# DONGLE01.net
KiCad netlist of a schematic drawn in Altium Designer
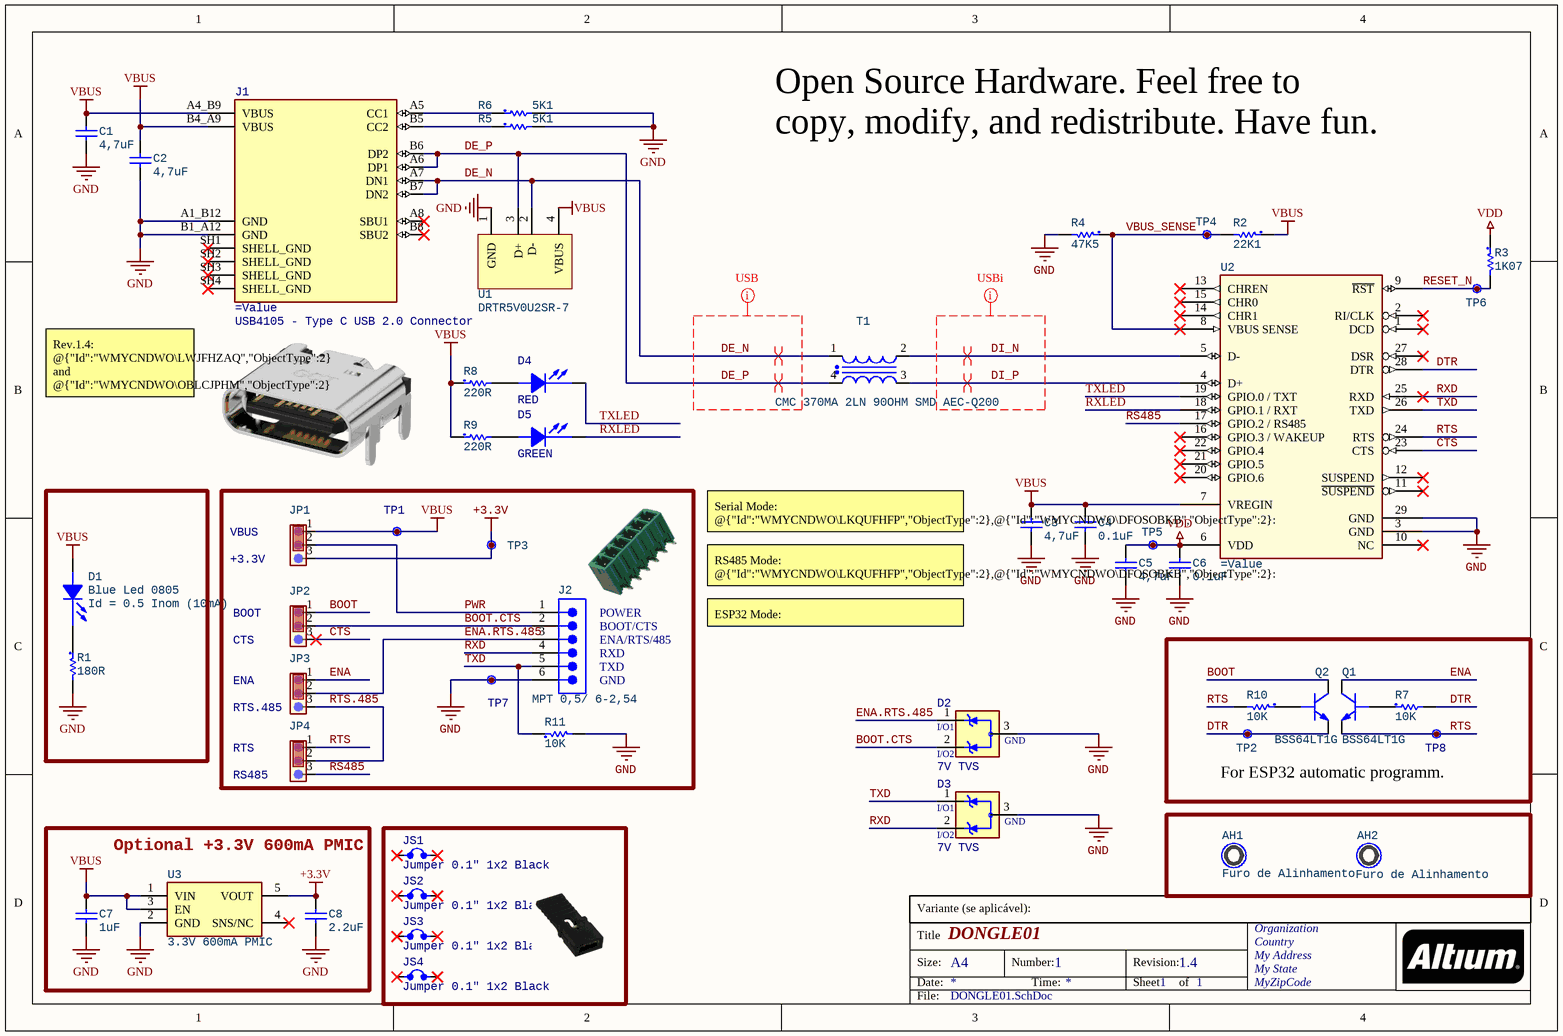
[diagram p0: DONGLE01.SchDoc]

(export (version "E")
  (design (tool "Eeschema 10.0.6"))
  (components
    (comp (ref "AH1")
      (value "Furo de Alinhamento")
      (footprint "AH_2.0MMD")
      (libsource (lib "My_Library") (part "Aligment Hole M2"))
    )
    (comp (ref "AH2")
      (value "Furo de Alinhamento")
      (footprint "AH_2.0MMD")
      (libsource (lib "My_Library") (part "Aligment Hole M2"))
    )
    (comp (ref "C1")
      (value "4,7uF")
      (footprint "C0805")
      (description "4.7 µF ±5% 25V Capacitor de cerâmica X7R 0805 (métrico 2012)")
      (fields (field (name "MANUFACTURER") "KEMET"))
      (libsource (lib "My_Library") (part "CAP"))
    )
    (comp (ref "C2")
      (value "4,7uF")
      (footprint "C0805")
      (description "4.7 µF ±5% 25V Capacitor de cerâmica X7R 0805 (métrico 2012)")
      (fields (field (name "MANUFACTURER") "KEMET"))
      (libsource (lib "My_Library") (part "CAP"))
    )
    (comp (ref "C3")
      (value "4,7uF")
      (footprint "C0805")
      (description "4.7 µF ±5% 25V Capacitor de cerâmica X7R 0805 (métrico 2012)")
      (fields (field (name "MANUFACTURER") "KEMET"))
      (libsource (lib "My_Library") (part "CAP"))
    )
    (comp (ref "C4")
      (value "0.1uF")
      (footprint "C0805")
      (description "0.1 µF ±10% 100V Ceramic Capacitor X7R 0805 (2012 Metric)")
      (fields (field (name "MANUFACTURER") "Murata Electronics"))
      (libsource (lib "My_Library") (part "CAP"))
    )
    (comp (ref "C5")
      (value "4,7uF")
      (footprint "C0805")
      (description "4.7 µF ±5% 25V Capacitor de cerâmica X7R 0805 (métrico 2012)")
      (fields (field (name "MANUFACTURER") "KEMET"))
      (libsource (lib "My_Library") (part "CAP"))
    )
    (comp (ref "C6")
      (value "0.1uF")
      (footprint "C0805")
      (description "0.1 µF ±10% 100V Ceramic Capacitor X7R 0805 (2012 Metric)")
      (fields (field (name "MANUFACTURER") "Murata Electronics"))
      (libsource (lib "My_Library") (part "CAP"))
    )
    (comp (ref "C7")
      (value "1uF")
      (footprint "C0805")
      (description "1 µF ±5% 16V Ceramic Capacitor X7R 0805 (2012 Metric)")
      (fields (field (name "MANUFACTURER") "KEMET"))
      (libsource (lib "My_Library") (part "CAP"))
    )
    (comp (ref "C8")
      (value "2.2uF")
      (footprint "C0805")
      (description "2.2 µF ±5% 16V Ceramic Capacitor X7R 0805 (2012 Metric)")
      (fields (field (name "MANUFACTURER") "KEMET"))
      (libsource (lib "My_Library") (part "CAP"))
    )
    (comp (ref "D1")
      (value "Blue Led 0805")
      (footprint "LED 0805")
      (description "Blue 470nm LED Indication - Discrete 3.2V 0805 (2012 Metric)")
      (fields (field (name "MANUFACTURER") "Würth Elektronik") (field (name "INFO") "Id = 0.5 Inom (10mA)"))
      (libsource (lib "My_Library") (part "LED GREEN 0805"))
    )
    (comp (ref "D2")
      (value "7V TVS")
      (footprint "WE-TVS_SOT23-3L")
      (description "7V Clamp 15A (8/20µs) Ipp Tvs Diode Surface Mount SOT-23-3")
      (fields (field (name "MANUFACTURER") "Würth Elektronik"))
      (libsource (lib "My_Library") (part "WE-TVS_SOT23-3L_824021"))
    )
    (comp (ref "D3")
      (value "7V TVS")
      (footprint "WE-TVS_SOT23-3L")
      (description "7V Clamp 15A (8/20µs) Ipp Tvs Diode Surface Mount SOT-23-3")
      (fields (field (name "MANUFACTURER") "Würth Elektronik"))
      (libsource (lib "My_Library") (part "WE-TVS_SOT23-3L_824021"))
    )
    (comp (ref "D4")
      (value "RED")
      (footprint "LED 0805")
      (description "Led Vermelho SMD 0805")
      (libsource (lib "My_Library") (part "LED RED 0805"))
    )
    (comp (ref "D5")
      (value "GREEN")
      (footprint "LED 0805")
      (description "Led Verde SMD 0805")
      (libsource (lib "My_Library") (part "LED GREEN 0805"))
    )
    (comp (ref "J1")
      (value "~")
      (footprint "GCT_USB4105-GF-A-060")
      (fields
        (field (name "INFO") "USB4105 - Type C USB 2.0 Connector")
        (field (name "MANUFACTURER") "Global Connector Technology")
      )
      (libsource (lib "My_Library") (part "USB4105-GF-A-060"))
    )
    (comp (ref "J2")
      (value "MPT 0,5/ 6-2,54")
      (footprint "1725698")
      (description "6 Position Wire to Board Terminal Block Horizontal with Board 0.100\" (2.54mm) Through Hole")
      (fields (field (name "MANUFACTURER") "Phoenix Contact"))
      (libsource (lib "691101710002_Altium_WR-TBL_rev23c") (part "691322110006"))
    )
    (comp (ref "JP1")
      (value "Header 3 Pin")
      (footprint "JMP-3-PTH-180")
      (description "3 Pin Jumper")
      (fields (field (name "MANUFACTURER") "Würth Elektronik"))
      (libsource (lib "My_Library") (part "Jumper 3"))
    )
    (comp (ref "JP2")
      (value "Header 3 Pin")
      (footprint "JMP-3-PTH-180")
      (description "3 Pin Jumper")
      (fields (field (name "MANUFACTURER") "Würth Elektronik"))
      (libsource (lib "My_Library") (part "Jumper 3"))
    )
    (comp (ref "JP3")
      (value "Header 3 Pin")
      (footprint "JMP-3-PTH-180")
      (description "3 Pin Jumper")
      (fields (field (name "MANUFACTURER") "Würth Elektronik"))
      (libsource (lib "My_Library") (part "Jumper 3"))
    )
    (comp (ref "JP4")
      (value "Header 3 Pin")
      (footprint "JMP-3-PTH-180")
      (description "3 Pin Jumper")
      (fields (field (name "MANUFACTURER") "Würth Elektronik"))
      (libsource (lib "My_Library") (part "Jumper 3"))
    )
    (comp (ref "JS1")
      (value "Jumper 0.1\" 1x2 Black")
      (description "2 (1 x 2) Position Shunt Connector Open Top, Grip 0.100\" (2.54mm) Gold")
      (fields (field (name "MANUFACTURER") "Sullins Connector Solutions"))
      (libsource (lib "My_Library") (part "Jumper 2"))
    )
    (comp (ref "JS2")
      (value "Jumper 0.1\" 1x2 Black")
      (description "2 (1 x 2) Position Shunt Connector Open Top, Grip 0.100\" (2.54mm) Gold")
      (fields (field (name "MANUFACTURER") "Sullins Connector Solutions"))
      (libsource (lib "My_Library") (part "Jumper 2"))
    )
    (comp (ref "JS3")
      (value "Jumper 0.1\" 1x2 Black")
      (description "2 (1 x 2) Position Shunt Connector Open Top, Grip 0.100\" (2.54mm) Gold")
      (fields (field (name "MANUFACTURER") "Sullins Connector Solutions"))
      (libsource (lib "My_Library") (part "Jumper 2"))
    )
    (comp (ref "JS4")
      (value "Jumper 0.1\" 1x2 Black")
      (description "2 (1 x 2) Position Shunt Connector Open Top, Grip 0.100\" (2.54mm) Gold")
      (fields (field (name "MANUFACTURER") "Sullins Connector Solutions"))
      (libsource (lib "My_Library") (part "Jumper 2"))
    )
    (comp (ref "Q1")
      (value "BSS64LT1G")
      (footprint "SOT-23")
      (description "Bipolar (BJT) Transistor NPN 80 V 100 mA 60MHz 225 mW Surface Mount SOT-23-3 (TO-236)")
      (fields (field (name "MANUFACTURER") "onsemi"))
      (libsource (lib "My_Library") (part "TR-NPN-BC817-SOT23"))
    )
    (comp (ref "Q2")
      (value "BSS64LT1G")
      (footprint "SOT-23")
      (description "Bipolar (BJT) Transistor NPN 80 V 100 mA 60MHz 225 mW Surface Mount SOT-23-3 (TO-236)")
      (fields (field (name "MANUFACTURER") "onsemi"))
      (libsource (lib "My_Library") (part "TR-NPN-BC817-SOT23"))
    )
    (comp (ref "R1")
      (value "180R")
      (footprint "R0805")
      (description "180 Ohms ±1% 0.25W, 1/4W Chip Resistor 0805 (2012 Metric) Anti-Sulfur Thin Film")
      (fields (field (name "MANUFACTURER") "Stackpole Electronics Inc"))
      (libsource (lib "My_Library") (part "RESISTOR"))
    )
    (comp (ref "R2")
      (value "22K1")
      (footprint "R0805")
      (fields (field (name "MANUFACTURER") "Bourns Inc."))
      (libsource (lib "My_Library") (part "RESISTOR"))
    )
    (comp (ref "R3")
      (value "1K07")
      (footprint "R0805")
      (description "1.07 kOhms ±1% 0.125W, 1/8W Chip Resistor 0805 (2012 Metric) Automotive AEC-Q200 Thick Film")
      (fields (field (name "MANUFACTURER") "Vishay Dale"))
      (libsource (lib "My_Library") (part "RESISTOR"))
    )
    (comp (ref "R4")
      (value "47K5")
      (footprint "R0805")
      (description "47.5 kOhms ±1% 0.125W, 1/8W Chip Resistor 0805 (2012 Metric) Moisture Resistant Thick Film")
      (fields (field (name "MANUFACTURER") "Bourns Inc."))
      (libsource (lib "My_Library") (part "RESISTOR"))
    )
    (comp (ref "R5")
      (value "5K1")
      (footprint "R0805")
      (description "5.1 kOhms ±1% 0.125W, 1/8W Chip Resistor 0805 (2012 Metric) Moisture Resistant Thick Film")
      (fields (field (name "MANUFACTURER") "YAGEO"))
      (libsource (lib "My_Library") (part "RESISTOR"))
    )
    (comp (ref "R6")
      (value "5K1")
      (footprint "R0805")
      (description "5.1 kOhms ±1% 0.125W, 1/8W Chip Resistor 0805 (2012 Metric) Moisture Resistant Thick Film")
      (fields (field (name "MANUFACTURER") "YAGEO"))
      (libsource (lib "My_Library") (part "RESISTOR"))
    )
    (comp (ref "R7")
      (value "10K")
      (footprint "R0805")
      (description "10 kOhms ±1% 0.125W, 1/8W Chip Resistor 0805 (2012 Metric) Automotive AEC-Q200 Thick Film")
      (fields (field (name "MANUFACTURER") "Stackpole Electronics Inc"))
      (libsource (lib "My_Library") (part "RESISTOR"))
    )
    (comp (ref "R8")
      (value "220R")
      (footprint "R0805")
      (description "10 kOhms ±1% 0.125W, 1/8W Chip Resistor 0805 (2012 Metric) Automotive AEC-Q200 Thick Film")
      (fields (field (name "MANUFACTURER") "Stackpole Electronics Inc"))
      (libsource (lib "My_Library") (part "RESISTOR"))
    )
    (comp (ref "R9")
      (value "220R")
      (footprint "R0805")
      (description "10 kOhms ±1% 0.125W, 1/8W Chip Resistor 0805 (2012 Metric) Automotive AEC-Q200 Thick Film")
      (fields (field (name "MANUFACTURER") "Stackpole Electronics Inc"))
      (libsource (lib "My_Library") (part "RESISTOR"))
    )
    (comp (ref "R10")
      (value "10K")
      (footprint "R0805")
      (description "10 kOhms ±1% 0.125W, 1/8W Chip Resistor 0805 (2012 Metric) Automotive AEC-Q200 Thick Film")
      (fields (field (name "MANUFACTURER") "Stackpole Electronics Inc"))
      (libsource (lib "My_Library") (part "RESISTOR"))
    )
    (comp (ref "R11")
      (value "10K")
      (footprint "R0805")
      (description "10 kOhms ±1% 0.125W, 1/8W Chip Resistor 0805 (2012 Metric) Automotive AEC-Q200 Thick Film")
      (fields (field (name "MANUFACTURER") "Stackpole Electronics Inc"))
      (libsource (lib "My_Library") (part "RESISTOR"))
    )
    (comp (ref "T1")
      (value "CMC 370MA 2LN 90OHM SMD AEC-Q200")
      (footprint "744232090")
      (description "2 Line Common Mode Choke Surface Mount 90 Ohms @ 100 MHz 370mA DCR 300mOhm")
      (fields (field (name "MANUFACTURER") "Würth Elektronik"))
      (libsource (lib "My_Library") (part "USB EMI FILTER"))
    )
    (comp (ref "TP1") (value "~") (footprint "TP") (libsource (lib "My_Library") (part "TESTPOINT")))
    (comp (ref "TP2") (value "~") (footprint "TP") (libsource (lib "My_Library") (part "TESTPOINT")))
    (comp (ref "TP3") (value "~") (footprint "TP") (libsource (lib "My_Library") (part "TESTPOINT")))
    (comp (ref "TP4") (value "~") (footprint "TP") (libsource (lib "My_Library") (part "TESTPOINT")))
    (comp (ref "TP5") (value "~") (footprint "TP") (libsource (lib "My_Library") (part "TESTPOINT")))
    (comp (ref "TP6") (value "~") (footprint "TP") (libsource (lib "My_Library") (part "TESTPOINT")))
    (comp (ref "TP7") (value "~") (footprint "TP") (libsource (lib "My_Library") (part "TESTPOINT")))
    (comp (ref "TP8") (value "~") (footprint "TP") (libsource (lib "My_Library") (part "TESTPOINT")))
    (comp (ref "U1")
      (value "USB ESD protection")
      (footprint "SOT143-4")
      (description "Clamp Ipp Tvs Diode Surface Mount SOT-143")
      (fields
        (field (name "MANUFACTURER P/N") "DRTR5V0U2SR-7")
        (field (name "MANUFACTURER") "Diodes Incorporated")
      )
      (libsource (lib "My_Library") (part "USB2.0_TVS_DIODES"))
    )
    (comp (ref "U2")
      (value "~")
      (footprint "QFN50P500X500X80_HS-29N CP2102N")
      (description "USB Bridge, USB to UART USB 2.0 UART Interface 28-QFN (5x5)")
      (fields (field (name "MANUFACTURER") "Silicon Labs"))
      (libsource (lib "My_Library") (part "CP2102N QFN28"))
    )
    (comp (ref "U3")
      (value "3.3V 600mA PMIC")
      (footprint "SOT94P280X100-5N")
      (description "Linear Voltage Regulator IC Positive Fixed 1 Output 600mA TSOT-23-5")
      (fields (field (name "MANUFACTURER") "Richtek USA Inc."))
      (libsource (lib "*") (part "RT9080-33GJ5"))
    )
  )
  (nets
    (net (code "1") (name "+3.3V") (class "Default")
      (node (ref "C8") (pin "1") (pinfunction "1_1") (pintype "passive"))
      (node (ref "JP1") (pin "3") (pinfunction "3_3") (pintype "passive"))
      (node (ref "TP3") (pin "1") (pinfunction "A_1") (pintype "passive"))
      (node (ref "U3") (pin "5") (pinfunction "VOUT_5") (pintype "power_in"))
    )
    (net (code "2") (name "/BOOT") (class "Default")
      (node (ref "JP2") (pin "1") (pinfunction "1_1") (pintype "passive"))
      (node (ref "Q2") (pin "3") (pinfunction "C_3") (pintype "passive"))
    )
    (net (code "3") (name "/BOOT.CTS") (class "Default")
      (node (ref "D2") (pin "2") (pinfunction "I/O2_2") (pintype "passive"))
      (node (ref "J2") (pin "2") (pinfunction "2_2") (pintype "passive"))
      (node (ref "JP2") (pin "2") (pinfunction "2_2") (pintype "passive"))
    )
    (net (code "4") (name "/CTS") (class "Default")
      (node (ref "JP2") (pin "3") (pinfunction "3_3") (pintype "passive"))
      (node (ref "U2") (pin "23") (pinfunction "CTS_23") (pintype "input"))
    )
    (net (code "5") (name "/DE_N") (class "Default")
      (node (ref "J1") (pin "A7") (pinfunction "DN1_A7") (pintype "bidirectional"))
      (node (ref "J1") (pin "B7") (pinfunction "DN2_B7") (pintype "bidirectional"))
      (node (ref "T1") (pin "1") (pinfunction "1_1") (pintype "passive"))
      (node (ref "U1") (pin "2") (pinfunction "D-_2") (pintype "passive"))
    )
    (net (code "6") (name "/DE_P") (class "Default")
      (node (ref "J1") (pin "A6") (pinfunction "DP1_A6") (pintype "bidirectional"))
      (node (ref "J1") (pin "B6") (pinfunction "DP2_B6") (pintype "bidirectional"))
      (node (ref "T1") (pin "4") (pinfunction "4_4") (pintype "passive"))
      (node (ref "U1") (pin "3") (pinfunction "D+_3") (pintype "passive"))
    )
    (net (code "7") (name "/DI_N") (class "Default")
      (node (ref "T1") (pin "2") (pinfunction "2_2") (pintype "passive"))
      (node (ref "U2") (pin "5") (pinfunction "D-_5") (pintype "bidirectional"))
    )
    (net (code "8") (name "/DI_P") (class "Default")
      (node (ref "T1") (pin "3") (pinfunction "3_3") (pintype "passive"))
      (node (ref "U2") (pin "4") (pinfunction "D+_4") (pintype "bidirectional"))
    )
    (net (code "9") (name "/DTR") (class "Default")
      (node (ref "Q2") (pin "2") (pinfunction "E_2") (pintype "passive"))
      (node (ref "R7") (pin "2") (pinfunction "2_2") (pintype "passive"))
      (node (ref "TP2") (pin "1") (pinfunction "A_1") (pintype "passive"))
      (node (ref "U2") (pin "28") (pinfunction "DTR_28") (pintype "output"))
    )
    (net (code "10") (name "/ENA") (class "Default")
      (node (ref "JP3") (pin "1") (pinfunction "1_1") (pintype "passive"))
      (node (ref "Q1") (pin "3") (pinfunction "C_3") (pintype "passive"))
    )
    (net (code "11") (name "/ENA.RTS.485") (class "Default")
      (node (ref "D2") (pin "1") (pinfunction "I/O1_1") (pintype "passive"))
      (node (ref "J2") (pin "3") (pinfunction "3_3") (pintype "passive"))
      (node (ref "JP3") (pin "2") (pinfunction "2_2") (pintype "passive"))
    )
    (net (code "12") (name "/PWR") (class "Default")
      (node (ref "J2") (pin "1") (pinfunction "1_1") (pintype "passive"))
      (node (ref "JP1") (pin "2") (pinfunction "2_2") (pintype "passive"))
    )
    (net (code "13") (name "/RESET_N") (class "Default")
      (node (ref "R3") (pin "2") (pinfunction "2_2") (pintype "passive"))
      (node (ref "TP6") (pin "1") (pinfunction "A_1") (pintype "passive"))
      (node (ref "U2") (pin "9") (pinfunction "~{RST}_9") (pintype "bidirectional"))
    )
    (net (code "14") (name "/RS485") (class "Default")
      (node (ref "JP4") (pin "3") (pinfunction "3_3") (pintype "passive"))
      (node (ref "U2") (pin "17") (pinfunction "GPIO.2_/_RS485_17") (pintype "bidirectional"))
    )
    (net (code "15") (name "/RTS") (class "Default")
      (node (ref "JP4") (pin "1") (pinfunction "1_1") (pintype "passive"))
      (node (ref "Q1") (pin "2") (pinfunction "E_2") (pintype "passive"))
      (node (ref "R10") (pin "2") (pinfunction "2_2") (pintype "passive"))
      (node (ref "TP8") (pin "1") (pinfunction "A_1") (pintype "passive"))
      (node (ref "U2") (pin "24") (pinfunction "RTS_24") (pintype "output"))
    )
    (net (code "16") (name "/RTS.485") (class "Default")
      (node (ref "JP3") (pin "3") (pinfunction "3_3") (pintype "passive"))
      (node (ref "JP4") (pin "2") (pinfunction "2_2") (pintype "passive"))
    )
    (net (code "17") (name "/RXD") (class "Default")
      (node (ref "D3") (pin "2") (pinfunction "I/O2_2") (pintype "passive"))
      (node (ref "J2") (pin "4") (pinfunction "4_4") (pintype "passive"))
      (node (ref "U2") (pin "25") (pinfunction "RXD_25") (pintype "input"))
    )
    (net (code "18") (name "/RXLED") (class "Default")
      (node (ref "D5") (pin "K") (pinfunction "K_K") (pintype "passive"))
      (node (ref "U2") (pin "18") (pinfunction "GPIO.1_/_RXT_18") (pintype "bidirectional"))
    )
    (net (code "19") (name "/TXD") (class "Default")
      (node (ref "D3") (pin "1") (pinfunction "I/O1_1") (pintype "passive"))
      (node (ref "J2") (pin "5") (pinfunction "5_5") (pintype "passive"))
      (node (ref "R11") (pin "1") (pinfunction "1_1") (pintype "passive"))
      (node (ref "U2") (pin "26") (pinfunction "TXD_26") (pintype "output"))
    )
    (net (code "20") (name "/TXLED") (class "Default")
      (node (ref "D4") (pin "K") (pinfunction "K_K") (pintype "passive"))
      (node (ref "U2") (pin "19") (pinfunction "GPIO.0_/_TXT_19") (pintype "bidirectional"))
    )
    (net (code "21") (name "/VBUS_SENSE") (class "Default")
      (node (ref "R2") (pin "2") (pinfunction "2_2") (pintype "passive"))
      (node (ref "R4") (pin "1") (pinfunction "1_1") (pintype "passive"))
      (node (ref "TP4") (pin "1") (pinfunction "A_1") (pintype "passive"))
      (node (ref "U2") (pin "8") (pinfunction "VBUS_SENSE_8") (pintype "input"))
    )
    (net (code "22") (name "GND") (class "Default")
      (node (ref "C1") (pin "2") (pinfunction "2_2") (pintype "passive"))
      (node (ref "C2") (pin "2") (pinfunction "2_2") (pintype "passive"))
      (node (ref "C3") (pin "2") (pinfunction "2_2") (pintype "passive"))
      (node (ref "C4") (pin "2") (pinfunction "2_2") (pintype "passive"))
      (node (ref "C5") (pin "2") (pinfunction "2_2") (pintype "passive"))
      (node (ref "C6") (pin "2") (pinfunction "2_2") (pintype "passive"))
      (node (ref "C7") (pin "2") (pinfunction "2_2") (pintype "passive"))
      (node (ref "C8") (pin "2") (pinfunction "2_2") (pintype "passive"))
      (node (ref "D2") (pin "3") (pinfunction "GND_3") (pintype "passive"))
      (node (ref "D3") (pin "3") (pinfunction "GND_3") (pintype "passive"))
      (node (ref "J1") (pin "A1_B12") (pinfunction "GND_A1_B12") (pintype "power_in"))
      (node (ref "J1") (pin "B1_A12") (pinfunction "GND_B1_A12") (pintype "power_in"))
      (node (ref "J2") (pin "6") (pinfunction "6_6") (pintype "passive"))
      (node (ref "R1") (pin "2") (pinfunction "2_2") (pintype "passive"))
      (node (ref "R11") (pin "2") (pinfunction "2_2") (pintype "passive"))
      (node (ref "R4") (pin "2") (pinfunction "2_2") (pintype "passive"))
      (node (ref "R5") (pin "2") (pinfunction "2_2") (pintype "passive"))
      (node (ref "R6") (pin "2") (pinfunction "2_2") (pintype "passive"))
      (node (ref "TP7") (pin "1") (pinfunction "A_1") (pintype "passive"))
      (node (ref "U1") (pin "1") (pinfunction "GND_1") (pintype "power_in"))
      (node (ref "U2") (pin "29") (pinfunction "GND_29") (pintype "power_in"))
      (node (ref "U2") (pin "3") (pinfunction "GND_3") (pintype "power_in"))
      (node (ref "U3") (pin "2") (pinfunction "GND_2") (pintype "power_in"))
    )
    (net (code "23") (name "Net-(D1-PadK)") (class "Default")
      (node (ref "D1") (pin "K") (pinfunction "K_K") (pintype "passive"))
      (node (ref "R1") (pin "1") (pinfunction "1_1") (pintype "passive"))
    )
    (net (code "24") (name "Net-(D4-PadA)") (class "Default")
      (node (ref "D4") (pin "A") (pinfunction "A_A") (pintype "passive"))
      (node (ref "R8") (pin "2") (pinfunction "2_2") (pintype "passive"))
    )
    (net (code "25") (name "Net-(D5-PadA)") (class "Default")
      (node (ref "D5") (pin "A") (pinfunction "A_A") (pintype "passive"))
      (node (ref "R9") (pin "2") (pinfunction "2_2") (pintype "passive"))
    )
    (net (code "26") (name "Net-(J1-CC1)") (class "Default")
      (node (ref "J1") (pin "A5") (pinfunction "CC1_A5") (pintype "bidirectional"))
      (node (ref "R6") (pin "1") (pinfunction "1_1") (pintype "passive"))
    )
    (net (code "27") (name "Net-(J1-CC2)") (class "Default")
      (node (ref "J1") (pin "B5") (pinfunction "CC2_B5") (pintype "bidirectional"))
      (node (ref "R5") (pin "1") (pinfunction "1_1") (pintype "passive"))
    )
    (net (code "28") (name "Net-(Q1-B)") (class "Default")
      (node (ref "Q1") (pin "1") (pinfunction "B_1") (pintype "passive"))
      (node (ref "R7") (pin "1") (pinfunction "1_1") (pintype "passive"))
    )
    (net (code "29") (name "Net-(Q2-B)") (class "Default")
      (node (ref "Q2") (pin "1") (pinfunction "B_1") (pintype "passive"))
      (node (ref "R10") (pin "1") (pinfunction "1_1") (pintype "passive"))
    )
    (net (code "30") (name "VBUS") (class "Default")
      (node (ref "C1") (pin "1") (pinfunction "1_1") (pintype "passive"))
      (node (ref "C2") (pin "1") (pinfunction "1_1") (pintype "passive"))
      (node (ref "C3") (pin "1") (pinfunction "1_1") (pintype "passive"))
      (node (ref "C4") (pin "1") (pinfunction "1_1") (pintype "passive"))
      (node (ref "C7") (pin "1") (pinfunction "1_1") (pintype "passive"))
      (node (ref "D1") (pin "A") (pinfunction "A_A") (pintype "passive"))
      (node (ref "J1") (pin "A4_B9") (pinfunction "VBUS_A4_B9") (pintype "power_in"))
      (node (ref "J1") (pin "B4_A9") (pinfunction "VBUS_B4_A9") (pintype "power_in"))
      (node (ref "JP1") (pin "1") (pinfunction "1_1") (pintype "passive"))
      (node (ref "R2") (pin "1") (pinfunction "1_1") (pintype "passive"))
      (node (ref "R8") (pin "1") (pinfunction "1_1") (pintype "passive"))
      (node (ref "R9") (pin "1") (pinfunction "1_1") (pintype "passive"))
      (node (ref "TP1") (pin "1") (pinfunction "A_1") (pintype "passive"))
      (node (ref "U1") (pin "4") (pinfunction "VBUS_4") (pintype "power_in"))
      (node (ref "U2") (pin "7") (pinfunction "VREGIN_7") (pintype "power_in"))
      (node (ref "U3") (pin "1") (pinfunction "VIN_1") (pintype "power_in"))
      (node (ref "U3") (pin "3") (pinfunction "EN_3") (pintype "passive"))
    )
    (net (code "31") (name "VDD") (class "Default")
      (node (ref "C5") (pin "1") (pinfunction "1_1") (pintype "passive"))
      (node (ref "C6") (pin "1") (pinfunction "1_1") (pintype "passive"))
      (node (ref "R3") (pin "1") (pinfunction "1_1") (pintype "passive"))
      (node (ref "TP5") (pin "1") (pinfunction "A_1") (pintype "passive"))
      (node (ref "U2") (pin "6") (pinfunction "VDD_6") (pintype "power_in"))
    )
    (net (code "32") (name "unconnected-(J1-SBU1-PadA8)") (class "Default")
      (node (ref "J1") (pin "A8") (pinfunction "SBU1_A8") (pintype "bidirectional+no_connect"))
    )
    (net (code "33") (name "unconnected-(J1-SBU2-PadB8)") (class "Default")
      (node (ref "J1") (pin "B8") (pinfunction "SBU2_B8") (pintype "bidirectional+no_connect"))
    )
    (net (code "34") (name "unconnected-(J1-SHELL_GND-PadSH1)") (class "Default")
      (node (ref "J1") (pin "SH1") (pinfunction "SHELL_GND_SH1") (pintype "power_in+no_connect"))
    )
    (net (code "35") (name "unconnected-(J1-SHELL_GND-PadSH2)") (class "Default")
      (node (ref "J1") (pin "SH2") (pinfunction "SHELL_GND_SH2") (pintype "power_in+no_connect"))
    )
    (net (code "36") (name "unconnected-(J1-SHELL_GND-PadSH3)") (class "Default")
      (node (ref "J1") (pin "SH3") (pinfunction "SHELL_GND_SH3") (pintype "power_in+no_connect"))
    )
    (net (code "37") (name "unconnected-(J1-SHELL_GND-PadSH4)") (class "Default")
      (node (ref "J1") (pin "SH4") (pinfunction "SHELL_GND_SH4") (pintype "power_in+no_connect"))
    )
    (net (code "38") (name "unconnected-(JS1-Pad1)") (class "Default")
      (node (ref "JS1") (pin "1") (pinfunction "1_1") (pintype "passive+no_connect"))
    )
    (net (code "39") (name "unconnected-(JS1-Pad2)") (class "Default")
      (node (ref "JS1") (pin "2") (pinfunction "2_2") (pintype "passive+no_connect"))
    )
    (net (code "40") (name "unconnected-(JS2-Pad1)") (class "Default")
      (node (ref "JS2") (pin "1") (pinfunction "1_1") (pintype "passive+no_connect"))
    )
    (net (code "41") (name "unconnected-(JS2-Pad2)") (class "Default")
      (node (ref "JS2") (pin "2") (pinfunction "2_2") (pintype "passive+no_connect"))
    )
    (net (code "42") (name "unconnected-(JS3-Pad1)") (class "Default")
      (node (ref "JS3") (pin "1") (pinfunction "1_1") (pintype "passive+no_connect"))
    )
    (net (code "43") (name "unconnected-(JS3-Pad2)") (class "Default")
      (node (ref "JS3") (pin "2") (pinfunction "2_2") (pintype "passive+no_connect"))
    )
    (net (code "44") (name "unconnected-(JS4-Pad1)") (class "Default")
      (node (ref "JS4") (pin "1") (pinfunction "1_1") (pintype "passive+no_connect"))
    )
    (net (code "45") (name "unconnected-(JS4-Pad2)") (class "Default")
      (node (ref "JS4") (pin "2") (pinfunction "2_2") (pintype "passive+no_connect"))
    )
    (net (code "46") (name "unconnected-(U2-CHR0-Pad15)") (class "Default")
      (node (ref "U2") (pin "15") (pinfunction "CHR0_15") (pintype "output+no_connect"))
    )
    (net (code "47") (name "unconnected-(U2-CHR1-Pad14)") (class "Default")
      (node (ref "U2") (pin "14") (pinfunction "CHR1_14") (pintype "output+no_connect"))
    )
    (net (code "48") (name "unconnected-(U2-CHREN-Pad13)") (class "Default")
      (node (ref "U2") (pin "13") (pinfunction "CHREN_13") (pintype "output+no_connect"))
    )
    (net (code "49") (name "unconnected-(U2-DCD-Pad1)") (class "Default")
      (node (ref "U2") (pin "1") (pinfunction "DCD_1") (pintype "input+no_connect"))
    )
    (net (code "50") (name "unconnected-(U2-DSR-Pad27)") (class "Default")
      (node (ref "U2") (pin "27") (pinfunction "DSR_27") (pintype "input+no_connect"))
    )
    (net (code "51") (name "unconnected-(U2-GPIO.3_{slash}_WAKEUP-Pad16)") (class "Default")
      (node (ref "U2") (pin "16") (pinfunction "GPIO.3_/_WAKEUP_16") (pintype "bidirectional+no_connect"))
    )
    (net (code "52") (name "unconnected-(U2-GPIO.4-Pad22)") (class "Default")
      (node (ref "U2") (pin "22") (pinfunction "GPIO.4_22") (pintype "bidirectional+no_connect"))
    )
    (net (code "53") (name "unconnected-(U2-GPIO.5-Pad21)") (class "Default")
      (node (ref "U2") (pin "21") (pinfunction "GPIO.5_21") (pintype "bidirectional+no_connect"))
    )
    (net (code "54") (name "unconnected-(U2-GPIO.6-Pad20)") (class "Default")
      (node (ref "U2") (pin "20") (pinfunction "GPIO.6_20") (pintype "bidirectional+no_connect"))
    )
    (net (code "55") (name "unconnected-(U2-NC-Pad10)") (class "Default")
      (node (ref "U2") (pin "10") (pinfunction "NC_10") (pintype "passive+no_connect"))
    )
    (net (code "56") (name "unconnected-(U2-RI{slash}CLK-Pad2)") (class "Default")
      (node (ref "U2") (pin "2") (pinfunction "RI/CLK_2") (pintype "input+no_connect"))
    )
    (net (code "57") (name "unconnected-(U2-SUSPEND-Pad12)") (class "Default")
      (node (ref "U2") (pin "12") (pinfunction "SUSPEND_12") (pintype "output+no_connect"))
    )
    (net (code "58") (name "unconnected-(U2-~{SUSPEND}-Pad11)") (class "Default")
      (node (ref "U2") (pin "11") (pinfunction "~{SUSPEND}_11") (pintype "output+no_connect"))
    )
    (net (code "59") (name "unconnected-(U3-SNS{slash}NC-Pad4)") (class "Default")
      (node (ref "U3") (pin "4") (pinfunction "SNS/NC_4") (pintype "passive+no_connect"))
    )
  )
)
